# connector_boards.net
KiCad netlist of a schematic drawn in EAGLE
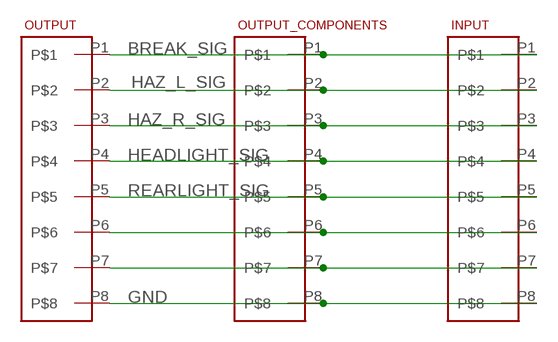
[diagram p0: schematic, sheet 1]

(export (version "E")
  (design (tool "Eeschema 10.0.6"))
  (components
    (comp (ref "INPUT")
      (value "8-PIN-MOLEX-RA-FEMALE")
      (footprint "eagle-import:8-PIN-MOLEX")
      (libsource (lib "eagle-import") (part "8-PIN-MOLEX-RA-FEMALE"))
    )
    (comp (ref "OUTPUT")
      (value "8-PIN-MOLEX-RA-FEMALE")
      (footprint "eagle-import:8-PIN-MOLEX")
      (libsource (lib "eagle-import") (part "8-PIN-MOLEX-RA-FEMALE"))
    )
    (comp (ref "OUTPUT_COMPONENTS")
      (value "8-PIN-MOLEX-RA-FEMALE")
      (footprint "eagle-import:8-PIN-MOLEX")
      (libsource (lib "eagle-import") (part "8-PIN-MOLEX-RA-FEMALE"))
    )
  )
  (nets
    (net (code "1") (name "/BREAK_SIG") (class "Default")
      (node (ref "INPUT") (pin "P1") (pinfunction "P$1_P1") (pintype "bidirectional"))
      (node (ref "OUTPUT") (pin "P1") (pinfunction "P$1_P1") (pintype "bidirectional"))
      (node (ref "OUTPUT_COMPONENTS") (pin "P1") (pinfunction "P$1_P1") (pintype "bidirectional"))
    )
    (net (code "2") (name "/GND") (class "Default")
      (node (ref "INPUT") (pin "P8") (pinfunction "P$8_P8") (pintype "bidirectional"))
      (node (ref "OUTPUT") (pin "P8") (pinfunction "P$8_P8") (pintype "bidirectional"))
      (node (ref "OUTPUT_COMPONENTS") (pin "P8") (pinfunction "P$8_P8") (pintype "bidirectional"))
    )
    (net (code "3") (name "/HAZ_L_SIG") (class "Default")
      (node (ref "INPUT") (pin "P2") (pinfunction "P$2_P2") (pintype "bidirectional"))
      (node (ref "OUTPUT") (pin "P2") (pinfunction "P$2_P2") (pintype "bidirectional"))
      (node (ref "OUTPUT_COMPONENTS") (pin "P2") (pinfunction "P$2_P2") (pintype "bidirectional"))
    )
    (net (code "4") (name "/HAZ_R_SIG") (class "Default")
      (node (ref "INPUT") (pin "P3") (pinfunction "P$3_P3") (pintype "bidirectional"))
      (node (ref "OUTPUT") (pin "P3") (pinfunction "P$3_P3") (pintype "bidirectional"))
      (node (ref "OUTPUT_COMPONENTS") (pin "P3") (pinfunction "P$3_P3") (pintype "bidirectional"))
    )
    (net (code "5") (name "/HEADLIGHT_SIG") (class "Default")
      (node (ref "INPUT") (pin "P4") (pinfunction "P$4_P4") (pintype "bidirectional"))
      (node (ref "OUTPUT") (pin "P4") (pinfunction "P$4_P4") (pintype "bidirectional"))
      (node (ref "OUTPUT_COMPONENTS") (pin "P4") (pinfunction "P$4_P4") (pintype "bidirectional"))
    )
    (net (code "6") (name "/REARLIGHT_SIG") (class "Default")
      (node (ref "INPUT") (pin "P5") (pinfunction "P$5_P5") (pintype "bidirectional"))
      (node (ref "OUTPUT") (pin "P5") (pinfunction "P$5_P5") (pintype "bidirectional"))
      (node (ref "OUTPUT_COMPONENTS") (pin "P5") (pinfunction "P$5_P5") (pintype "bidirectional"))
    )
    (net (code "7") (name "Net-(INPUT-P$6)") (class "Default")
      (node (ref "INPUT") (pin "P6") (pinfunction "P$6_P6") (pintype "bidirectional"))
      (node (ref "OUTPUT") (pin "P6") (pinfunction "P$6_P6") (pintype "bidirectional"))
      (node (ref "OUTPUT_COMPONENTS") (pin "P6") (pinfunction "P$6_P6") (pintype "bidirectional"))
    )
    (net (code "8") (name "Net-(INPUT-P$7)") (class "Default")
      (node (ref "INPUT") (pin "P7") (pinfunction "P$7_P7") (pintype "bidirectional"))
      (node (ref "OUTPUT") (pin "P7") (pinfunction "P$7_P7") (pintype "bidirectional"))
      (node (ref "OUTPUT_COMPONENTS") (pin "P7") (pinfunction "P$7_P7") (pintype "bidirectional"))
    )
  )
)
